# control.net
KiCad netlist of a schematic drawn in EAGLE
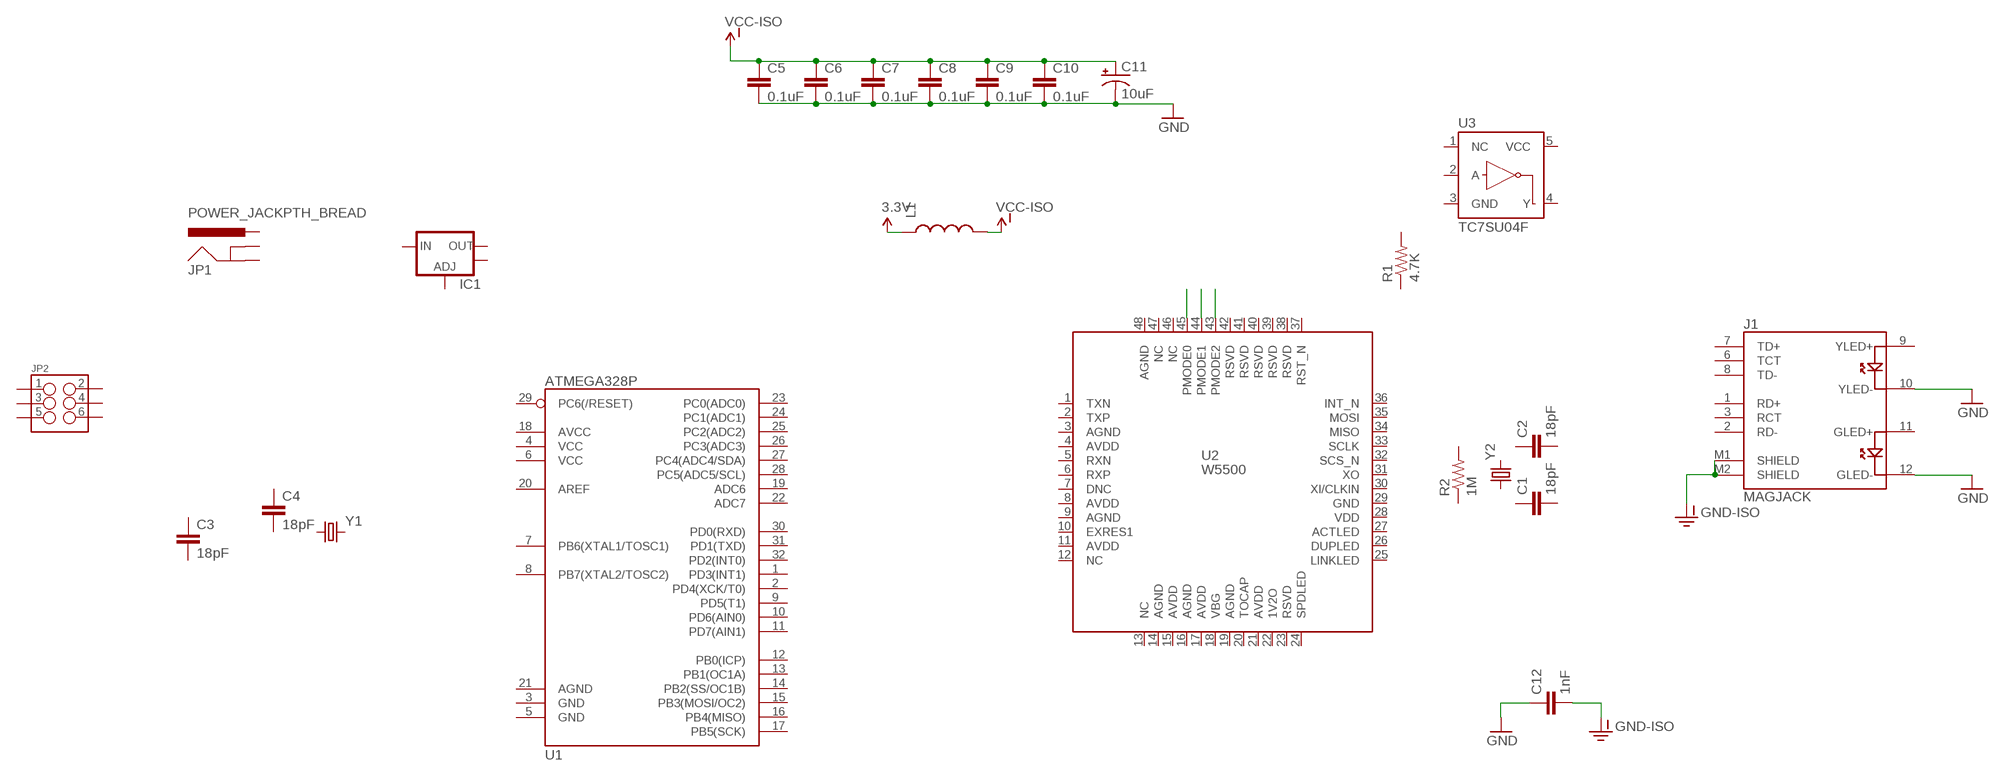
[diagram p0: schematic, sheet 1]

(export (version "E")
  (design (tool "Eeschema 10.0.6"))
  (components
    (comp (ref "C1")
      (value "18pF")
      (footprint "eagle-import:0603-CAP")
      (libsource (lib "eagle-import") (part "18PF-50V-5%(0603)"))
    )
    (comp (ref "C2")
      (value "18pF")
      (footprint "eagle-import:0603-CAP")
      (libsource (lib "eagle-import") (part "18PF-50V-5%(0603)"))
    )
    (comp (ref "C3")
      (value "18pF")
      (footprint "eagle-import:0603-CAP")
      (libsource (lib "eagle-import") (part "18PF-50V-5%(0603)"))
    )
    (comp (ref "C4")
      (value "18pF")
      (footprint "eagle-import:0603-CAP")
      (libsource (lib "eagle-import") (part "18PF-50V-5%(0603)"))
    )
    (comp (ref "C5")
      (value "0.1uF")
      (footprint "eagle-import:0603-CAP")
      (libsource (lib "eagle-import") (part "0.1UF-25V-5%(0603)"))
    )
    (comp (ref "C6")
      (value "0.1uF")
      (footprint "eagle-import:0603-CAP")
      (libsource (lib "eagle-import") (part "0.1UF-25V-5%(0603)"))
    )
    (comp (ref "C7")
      (value "0.1uF")
      (footprint "eagle-import:0603-CAP")
      (libsource (lib "eagle-import") (part "0.1UF-25V-5%(0603)"))
    )
    (comp (ref "C8")
      (value "0.1uF")
      (footprint "eagle-import:0603-CAP")
      (libsource (lib "eagle-import") (part "0.1UF-25V-5%(0603)"))
    )
    (comp (ref "C9")
      (value "0.1uF")
      (footprint "eagle-import:0603-CAP")
      (libsource (lib "eagle-import") (part "0.1UF-25V-5%(0603)"))
    )
    (comp (ref "C10")
      (value "0.1uF")
      (footprint "eagle-import:0603-CAP")
      (libsource (lib "eagle-import") (part "0.1UF-25V-5%(0603)"))
    )
    (comp (ref "C11")
      (value "10uF")
      (footprint "eagle-import:EIA3216")
      (libsource (lib "eagle-import") (part "10UF-16V-10%(TANT)"))
    )
    (comp (ref "C12")
      (value "1nF")
      (footprint "eagle-import:0603-CAP")
      (libsource (lib "eagle-import") (part "1NF/1000PF-50V-10%(0603)"))
    )
    (comp (ref "IC1")
      (value "V_REG_LM1117SOT223")
      (footprint "eagle-import:SOT223")
      (libsource (lib "eagle-import") (part "V_REG_LM1117SOT223"))
    )
    (comp (ref "J1")
      (value "MAGJACK")
      (footprint "eagle-import:MAGJACK")
      (libsource (lib "eagle-import") (part "MAGJACK"))
    )
    (comp (ref "JP1")
      (value "POWER_JACKPTH_BREAD")
      (footprint "eagle-import:POWER_JACK_PTH_BREAD")
      (libsource (lib "eagle-import") (part "POWER_JACKPTH_BREAD"))
    )
    (comp (ref "JP2")
      (value "M03X2SHROUD")
      (footprint "eagle-import:2X3-SHROUDED")
      (libsource (lib "eagle-import") (part "M03X2SHROUD"))
    )
    (comp (ref "L1")
      (value "INDUCTOR0603")
      (footprint "eagle-import:0603")
      (libsource (lib "eagle-import") (part "INDUCTOR0603"))
    )
    (comp (ref "R1")
      (value "4.7K")
      (footprint "eagle-import:0603-RES")
      (libsource (lib "eagle-import") (part "4.7KOHM-1/10W-1%(0603)"))
    )
    (comp (ref "R2")
      (value "1M")
      (footprint "eagle-import:0603-RES")
      (libsource (lib "eagle-import") (part "1MOHM-1/10W-1%(0603)"))
    )
    (comp (ref "U1")
      (value "ATMEGA328P")
      (footprint "eagle-import:TQFP32-08")
      (libsource (lib "eagle-import") (part "ATMEGA328_SMT"))
    )
    (comp (ref "U2")
      (value "W5500")
      (footprint "eagle-import:W5500")
      (libsource (lib "eagle-import") (part "W5500"))
    )
    (comp (ref "U3")
      (value "TC7SU04F")
      (footprint "eagle-import:SOT23-5")
      (libsource (lib "eagle-import") (part "INVERTER_SOT23-5"))
    )
    (comp (ref "Y1")
      (value "CRYSTALHC49US")
      (footprint "eagle-import:HC49US")
      (libsource (lib "eagle-import") (part "CRYSTALHC49US"))
    )
    (comp (ref "Y2")
      (value "CRYSTALHC49US")
      (footprint "eagle-import:HC49US")
      (libsource (lib "eagle-import") (part "CRYSTALHC49US"))
    )
  )
  (nets
    (net (code "1") (name "3.3V") (class "Default")
      (node (ref "L1") (pin "1") (pinfunction "1_1") (pintype "passive"))
    )
    (net (code "2") (name "GND") (class "Default")
      (node (ref "C10") (pin "2") (pinfunction "2_2") (pintype "passive"))
      (node (ref "C11") (pin "C") (pinfunction "-_C") (pintype "passive"))
      (node (ref "C12") (pin "1") (pinfunction "1_1") (pintype "passive"))
      (node (ref "C5") (pin "2") (pinfunction "2_2") (pintype "passive"))
      (node (ref "C6") (pin "2") (pinfunction "2_2") (pintype "passive"))
      (node (ref "C7") (pin "2") (pinfunction "2_2") (pintype "passive"))
      (node (ref "C8") (pin "2") (pinfunction "2_2") (pintype "passive"))
      (node (ref "C9") (pin "2") (pinfunction "2_2") (pintype "passive"))
      (node (ref "J1") (pin "10") (pinfunction "YLED-_10") (pintype "bidirectional"))
      (node (ref "J1") (pin "12") (pinfunction "GLED-_12") (pintype "bidirectional"))
    )
    (net (code "3") (name "GND-ISO") (class "Default")
      (node (ref "C12") (pin "2") (pinfunction "2_2") (pintype "passive"))
      (node (ref "J1") (pin "M1") (pinfunction "SHIELD_M1") (pintype "bidirectional"))
      (node (ref "J1") (pin "M2") (pinfunction "SHIELD_M2") (pintype "bidirectional"))
    )
    (net (code "4") (name "VCC-ISO") (class "Default")
      (node (ref "C10") (pin "1") (pinfunction "1_1") (pintype "passive"))
      (node (ref "C11") (pin "A") (pinfunction "+_A") (pintype "passive"))
      (node (ref "C5") (pin "1") (pinfunction "1_1") (pintype "passive"))
      (node (ref "C6") (pin "1") (pinfunction "1_1") (pintype "passive"))
      (node (ref "C7") (pin "1") (pinfunction "1_1") (pintype "passive"))
      (node (ref "C8") (pin "1") (pinfunction "1_1") (pintype "passive"))
      (node (ref "C9") (pin "1") (pinfunction "1_1") (pintype "passive"))
      (node (ref "L1") (pin "2") (pinfunction "2_2") (pintype "passive"))
    )
    (net (code "5") (name "unconnected-(C1-Pad1)") (class "Default")
      (node (ref "C1") (pin "1") (pinfunction "1_1") (pintype "passive"))
    )
    (net (code "6") (name "unconnected-(C1-Pad2)") (class "Default")
      (node (ref "C1") (pin "2") (pinfunction "2_2") (pintype "passive"))
    )
    (net (code "7") (name "unconnected-(C2-Pad1)") (class "Default")
      (node (ref "C2") (pin "1") (pinfunction "1_1") (pintype "passive"))
    )
    (net (code "8") (name "unconnected-(C2-Pad2)") (class "Default")
      (node (ref "C2") (pin "2") (pinfunction "2_2") (pintype "passive"))
    )
    (net (code "9") (name "unconnected-(C3-Pad1)") (class "Default")
      (node (ref "C3") (pin "1") (pinfunction "1_1") (pintype "passive"))
    )
    (net (code "10") (name "unconnected-(C3-Pad2)") (class "Default")
      (node (ref "C3") (pin "2") (pinfunction "2_2") (pintype "passive"))
    )
    (net (code "11") (name "unconnected-(C4-Pad1)") (class "Default")
      (node (ref "C4") (pin "1") (pinfunction "1_1") (pintype "passive"))
    )
    (net (code "12") (name "unconnected-(C4-Pad2)") (class "Default")
      (node (ref "C4") (pin "2") (pinfunction "2_2") (pintype "passive"))
    )
    (net (code "13") (name "unconnected-(IC1-ADJ-Pad1)") (class "Default")
      (node (ref "IC1") (pin "1") (pinfunction "ADJ_1") (pintype "input"))
    )
    (net (code "14") (name "unconnected-(IC1-IN-Pad3)") (class "Default")
      (node (ref "IC1") (pin "3") (pinfunction "IN_3") (pintype "input"))
    )
    (net (code "15") (name "unconnected-(IC1-OUT-Pad2)") (class "Default")
      (node (ref "IC1") (pin "2") (pinfunction "OUT_2") (pintype "output"))
    )
    (net (code "16") (name "unconnected-(IC1-OUT-Pad4)") (class "Default")
      (node (ref "IC1") (pin "4") (pinfunction "OUT_4") (pintype "output"))
    )
    (net (code "17") (name "unconnected-(J1-GLED+-Pad11)") (class "Default")
      (node (ref "J1") (pin "11") (pinfunction "GLED+_11") (pintype "bidirectional"))
    )
    (net (code "18") (name "unconnected-(J1-RCT-Pad3)") (class "Default")
      (node (ref "J1") (pin "3") (pinfunction "RCT_3") (pintype "bidirectional"))
    )
    (net (code "19") (name "unconnected-(J1-RD+-Pad1)") (class "Default")
      (node (ref "J1") (pin "1") (pinfunction "RD+_1") (pintype "bidirectional"))
    )
    (net (code "20") (name "unconnected-(J1-RD--Pad2)") (class "Default")
      (node (ref "J1") (pin "2") (pinfunction "RD-_2") (pintype "bidirectional"))
    )
    (net (code "21") (name "unconnected-(J1-TCT-Pad6)") (class "Default")
      (node (ref "J1") (pin "6") (pinfunction "TCT_6") (pintype "bidirectional"))
    )
    (net (code "22") (name "unconnected-(J1-TD+-Pad7)") (class "Default")
      (node (ref "J1") (pin "7") (pinfunction "TD+_7") (pintype "bidirectional"))
    )
    (net (code "23") (name "unconnected-(J1-TD--Pad8)") (class "Default")
      (node (ref "J1") (pin "8") (pinfunction "TD-_8") (pintype "bidirectional"))
    )
    (net (code "24") (name "unconnected-(J1-YLED+-Pad9)") (class "Default")
      (node (ref "J1") (pin "9") (pinfunction "YLED+_9") (pintype "bidirectional"))
    )
    (net (code "25") (name "unconnected-(JP1-PadGND)") (class "Default")
      (node (ref "JP1") (pin "GND") (pinfunction "GND_GND") (pintype "bidirectional"))
    )
    (net (code "26") (name "unconnected-(JP1-PadGNDBREAK)") (class "Default")
      (node (ref "JP1") (pin "GNDBREAK") (pinfunction "GNDBREAK_GNDBREAK") (pintype "bidirectional"))
    )
    (net (code "27") (name "unconnected-(JP1-PadPWR)") (class "Default")
      (node (ref "JP1") (pin "PWR") (pinfunction "PWR_PWR") (pintype "bidirectional"))
    )
    (net (code "28") (name "unconnected-(JP2-Pad1)") (class "Default")
      (node (ref "JP2") (pin "1") (pinfunction "1_1") (pintype "bidirectional"))
    )
    (net (code "29") (name "unconnected-(JP2-Pad2)") (class "Default")
      (node (ref "JP2") (pin "2") (pinfunction "2_2") (pintype "bidirectional"))
    )
    (net (code "30") (name "unconnected-(JP2-Pad3)") (class "Default")
      (node (ref "JP2") (pin "3") (pinfunction "3_3") (pintype "bidirectional"))
    )
    (net (code "31") (name "unconnected-(JP2-Pad4)") (class "Default")
      (node (ref "JP2") (pin "4") (pinfunction "4_4") (pintype "bidirectional"))
    )
    (net (code "32") (name "unconnected-(JP2-Pad5)") (class "Default")
      (node (ref "JP2") (pin "5") (pinfunction "5_5") (pintype "bidirectional"))
    )
    (net (code "33") (name "unconnected-(JP2-Pad6)") (class "Default")
      (node (ref "JP2") (pin "6") (pinfunction "6_6") (pintype "bidirectional"))
    )
    (net (code "34") (name "unconnected-(R1-Pad1)") (class "Default")
      (node (ref "R1") (pin "1") (pinfunction "1_1") (pintype "passive"))
    )
    (net (code "35") (name "unconnected-(R1-Pad2)") (class "Default")
      (node (ref "R1") (pin "2") (pinfunction "2_2") (pintype "passive"))
    )
    (net (code "36") (name "unconnected-(R2-Pad1)") (class "Default")
      (node (ref "R2") (pin "1") (pinfunction "1_1") (pintype "passive"))
    )
    (net (code "37") (name "unconnected-(R2-Pad2)") (class "Default")
      (node (ref "R2") (pin "2") (pinfunction "2_2") (pintype "passive"))
    )
    (net (code "38") (name "unconnected-(U1-ADC6-Pad19)") (class "Default")
      (node (ref "U1") (pin "19") (pinfunction "ADC6_19") (pintype "bidirectional"))
    )
    (net (code "39") (name "unconnected-(U1-ADC7-Pad22)") (class "Default")
      (node (ref "U1") (pin "22") (pinfunction "ADC7_22") (pintype "bidirectional"))
    )
    (net (code "40") (name "unconnected-(U1-AGND-Pad21)") (class "Default")
      (node (ref "U1") (pin "21") (pinfunction "AGND_21") (pintype "bidirectional"))
    )
    (net (code "41") (name "unconnected-(U1-AREF-Pad20)") (class "Default")
      (node (ref "U1") (pin "20") (pinfunction "AREF_20") (pintype "bidirectional"))
    )
    (net (code "42") (name "unconnected-(U1-AVCC-Pad18)") (class "Default")
      (node (ref "U1") (pin "18") (pinfunction "AVCC_18") (pintype "bidirectional"))
    )
    (net (code "43") (name "unconnected-(U1-GND-Pad3)") (class "Default")
      (node (ref "U1") (pin "3") (pinfunction "GND_3") (pintype "bidirectional"))
    )
    (net (code "44") (name "unconnected-(U1-GND-Pad5)") (class "Default")
      (node (ref "U1") (pin "5") (pinfunction "GND_5") (pintype "bidirectional"))
    )
    (net (code "45") (name "unconnected-(U1-PB0(ICP)-Pad12)") (class "Default")
      (node (ref "U1") (pin "12") (pinfunction "PB0(ICP)_12") (pintype "bidirectional"))
    )
    (net (code "46") (name "unconnected-(U1-PB1(OC1A)-Pad13)") (class "Default")
      (node (ref "U1") (pin "13") (pinfunction "PB1(OC1A)_13") (pintype "bidirectional"))
    )
    (net (code "47") (name "unconnected-(U1-PB2(SS{slash}OC1B)-Pad14)") (class "Default")
      (node (ref "U1") (pin "14") (pinfunction "PB2(SS/OC1B)_14") (pintype "bidirectional"))
    )
    (net (code "48") (name "unconnected-(U1-PB3(MOSI{slash}OC2)-Pad15)") (class "Default")
      (node (ref "U1") (pin "15") (pinfunction "PB3(MOSI/OC2)_15") (pintype "bidirectional"))
    )
    (net (code "49") (name "unconnected-(U1-PB4(MISO)-Pad16)") (class "Default")
      (node (ref "U1") (pin "16") (pinfunction "PB4(MISO)_16") (pintype "bidirectional"))
    )
    (net (code "50") (name "unconnected-(U1-PB5(SCK)-Pad17)") (class "Default")
      (node (ref "U1") (pin "17") (pinfunction "PB5(SCK)_17") (pintype "bidirectional"))
    )
    (net (code "51") (name "unconnected-(U1-PB6(XTAL1{slash}TOSC1)-Pad7)") (class "Default")
      (node (ref "U1") (pin "7") (pinfunction "PB6(XTAL1/TOSC1)_7") (pintype "bidirectional"))
    )
    (net (code "52") (name "unconnected-(U1-PB7(XTAL2{slash}TOSC2)-Pad8)") (class "Default")
      (node (ref "U1") (pin "8") (pinfunction "PB7(XTAL2/TOSC2)_8") (pintype "bidirectional"))
    )
    (net (code "53") (name "unconnected-(U1-PC0(ADC0)-Pad23)") (class "Default")
      (node (ref "U1") (pin "23") (pinfunction "PC0(ADC0)_23") (pintype "bidirectional"))
    )
    (net (code "54") (name "unconnected-(U1-PC1(ADC1)-Pad24)") (class "Default")
      (node (ref "U1") (pin "24") (pinfunction "PC1(ADC1)_24") (pintype "bidirectional"))
    )
    (net (code "55") (name "unconnected-(U1-PC2(ADC2)-Pad25)") (class "Default")
      (node (ref "U1") (pin "25") (pinfunction "PC2(ADC2)_25") (pintype "bidirectional"))
    )
    (net (code "56") (name "unconnected-(U1-PC3(ADC3)-Pad26)") (class "Default")
      (node (ref "U1") (pin "26") (pinfunction "PC3(ADC3)_26") (pintype "bidirectional"))
    )
    (net (code "57") (name "unconnected-(U1-PC4(ADC4{slash}SDA)-Pad27)") (class "Default")
      (node (ref "U1") (pin "27") (pinfunction "PC4(ADC4/SDA)_27") (pintype "bidirectional"))
    )
    (net (code "58") (name "unconnected-(U1-PC5(ADC5{slash}SCL)-Pad28)") (class "Default")
      (node (ref "U1") (pin "28") (pinfunction "PC5(ADC5/SCL)_28") (pintype "bidirectional"))
    )
    (net (code "59") (name "unconnected-(U1-PC6({slash}RESET)-Pad29)") (class "Default")
      (node (ref "U1") (pin "29") (pinfunction "PC6(/RESET)_29") (pintype "bidirectional"))
    )
    (net (code "60") (name "unconnected-(U1-PD0(RXD)-Pad30)") (class "Default")
      (node (ref "U1") (pin "30") (pinfunction "PD0(RXD)_30") (pintype "bidirectional"))
    )
    (net (code "61") (name "unconnected-(U1-PD1(TXD)-Pad31)") (class "Default")
      (node (ref "U1") (pin "31") (pinfunction "PD1(TXD)_31") (pintype "bidirectional"))
    )
    (net (code "62") (name "unconnected-(U1-PD2(INT0)-Pad32)") (class "Default")
      (node (ref "U1") (pin "32") (pinfunction "PD2(INT0)_32") (pintype "bidirectional"))
    )
    (net (code "63") (name "unconnected-(U1-PD3(INT1)-Pad1)") (class "Default")
      (node (ref "U1") (pin "1") (pinfunction "PD3(INT1)_1") (pintype "bidirectional"))
    )
    (net (code "64") (name "unconnected-(U1-PD4(XCK{slash}T0)-Pad2)") (class "Default")
      (node (ref "U1") (pin "2") (pinfunction "PD4(XCK/T0)_2") (pintype "bidirectional"))
    )
    (net (code "65") (name "unconnected-(U1-PD5(T1)-Pad9)") (class "Default")
      (node (ref "U1") (pin "9") (pinfunction "PD5(T1)_9") (pintype "bidirectional"))
    )
    (net (code "66") (name "unconnected-(U1-PD6(AIN0)-Pad10)") (class "Default")
      (node (ref "U1") (pin "10") (pinfunction "PD6(AIN0)_10") (pintype "bidirectional"))
    )
    (net (code "67") (name "unconnected-(U1-PD7(AIN1)-Pad11)") (class "Default")
      (node (ref "U1") (pin "11") (pinfunction "PD7(AIN1)_11") (pintype "bidirectional"))
    )
    (net (code "68") (name "unconnected-(U1-VCC-Pad4)") (class "Default")
      (node (ref "U1") (pin "4") (pinfunction "VCC_4") (pintype "bidirectional"))
    )
    (net (code "69") (name "unconnected-(U1-VCC-Pad6)") (class "Default")
      (node (ref "U1") (pin "6") (pinfunction "VCC_6") (pintype "bidirectional"))
    )
    (net (code "70") (name "unconnected-(U2-1V2O-Pad22)") (class "Default")
      (node (ref "U2") (pin "22") (pinfunction "1V2O_22") (pintype "passive"))
    )
    (net (code "71") (name "unconnected-(U2-ACTLED-Pad27)") (class "Default")
      (node (ref "U2") (pin "27") (pinfunction "ACTLED_27") (pintype "passive"))
    )
    (net (code "72") (name "unconnected-(U2-AGND-Pad3)") (class "Default")
      (node (ref "U2") (pin "3") (pinfunction "AGND_3") (pintype "passive"))
    )
    (net (code "73") (name "unconnected-(U2-AGND-Pad9)") (class "Default")
      (node (ref "U2") (pin "9") (pinfunction "AGND_9") (pintype "passive"))
    )
    (net (code "74") (name "unconnected-(U2-AGND-Pad14)") (class "Default")
      (node (ref "U2") (pin "14") (pinfunction "AGND_14") (pintype "passive"))
    )
    (net (code "75") (name "unconnected-(U2-AGND-Pad16)") (class "Default")
      (node (ref "U2") (pin "16") (pinfunction "AGND_16") (pintype "passive"))
    )
    (net (code "76") (name "unconnected-(U2-AGND-Pad19)") (class "Default")
      (node (ref "U2") (pin "19") (pinfunction "AGND_19") (pintype "passive"))
    )
    (net (code "77") (name "unconnected-(U2-AGND-Pad48)") (class "Default")
      (node (ref "U2") (pin "48") (pinfunction "AGND_48") (pintype "passive"))
    )
    (net (code "78") (name "unconnected-(U2-AVDD-Pad4)") (class "Default")
      (node (ref "U2") (pin "4") (pinfunction "AVDD_4") (pintype "passive"))
    )
    (net (code "79") (name "unconnected-(U2-AVDD-Pad8)") (class "Default")
      (node (ref "U2") (pin "8") (pinfunction "AVDD_8") (pintype "passive"))
    )
    (net (code "80") (name "unconnected-(U2-AVDD-Pad11)") (class "Default")
      (node (ref "U2") (pin "11") (pinfunction "AVDD_11") (pintype "passive"))
    )
    (net (code "81") (name "unconnected-(U2-AVDD-Pad15)") (class "Default")
      (node (ref "U2") (pin "15") (pinfunction "AVDD_15") (pintype "passive"))
    )
    (net (code "82") (name "unconnected-(U2-AVDD-Pad17)") (class "Default")
      (node (ref "U2") (pin "17") (pinfunction "AVDD_17") (pintype "passive"))
    )
    (net (code "83") (name "unconnected-(U2-AVDD-Pad21)") (class "Default")
      (node (ref "U2") (pin "21") (pinfunction "AVDD_21") (pintype "passive"))
    )
    (net (code "84") (name "unconnected-(U2-DNC-Pad7)") (class "Default")
      (node (ref "U2") (pin "7") (pinfunction "DNC_7") (pintype "passive"))
    )
    (net (code "85") (name "unconnected-(U2-DUPLED-Pad26)") (class "Default")
      (node (ref "U2") (pin "26") (pinfunction "DUPLED_26") (pintype "passive"))
    )
    (net (code "86") (name "unconnected-(U2-EXRES1-Pad10)") (class "Default")
      (node (ref "U2") (pin "10") (pinfunction "EXRES1_10") (pintype "passive"))
    )
    (net (code "87") (name "unconnected-(U2-GND-Pad29)") (class "Default")
      (node (ref "U2") (pin "29") (pinfunction "GND_29") (pintype "passive"))
    )
    (net (code "88") (name "unconnected-(U2-INT_N-Pad36)") (class "Default")
      (node (ref "U2") (pin "36") (pinfunction "INT_N_36") (pintype "passive"))
    )
    (net (code "89") (name "unconnected-(U2-LINKLED-Pad25)") (class "Default")
      (node (ref "U2") (pin "25") (pinfunction "LINKLED_25") (pintype "passive"))
    )
    (net (code "90") (name "unconnected-(U2-MISO-Pad34)") (class "Default")
      (node (ref "U2") (pin "34") (pinfunction "MISO_34") (pintype "passive"))
    )
    (net (code "91") (name "unconnected-(U2-MOSI-Pad35)") (class "Default")
      (node (ref "U2") (pin "35") (pinfunction "MOSI_35") (pintype "passive"))
    )
    (net (code "92") (name "unconnected-(U2-NC-Pad12)") (class "Default")
      (node (ref "U2") (pin "12") (pinfunction "NC_12") (pintype "passive"))
    )
    (net (code "93") (name "unconnected-(U2-NC-Pad13)") (class "Default")
      (node (ref "U2") (pin "13") (pinfunction "NC_13") (pintype "passive"))
    )
    (net (code "94") (name "unconnected-(U2-NC-Pad46)") (class "Default")
      (node (ref "U2") (pin "46") (pinfunction "NC_46") (pintype "passive"))
    )
    (net (code "95") (name "unconnected-(U2-NC-Pad47)") (class "Default")
      (node (ref "U2") (pin "47") (pinfunction "NC_47") (pintype "passive"))
    )
    (net (code "96") (name "unconnected-(U2-PMODE0-Pad45)") (class "Default")
      (node (ref "U2") (pin "45") (pinfunction "PMODE0_45") (pintype "passive"))
    )
    (net (code "97") (name "unconnected-(U2-PMODE1-Pad44)") (class "Default")
      (node (ref "U2") (pin "44") (pinfunction "PMODE1_44") (pintype "passive"))
    )
    (net (code "98") (name "unconnected-(U2-PMODE2-Pad43)") (class "Default")
      (node (ref "U2") (pin "43") (pinfunction "PMODE2_43") (pintype "passive"))
    )
    (net (code "99") (name "unconnected-(U2-RST_N-Pad37)") (class "Default")
      (node (ref "U2") (pin "37") (pinfunction "RST_N_37") (pintype "passive"))
    )
    (net (code "100") (name "unconnected-(U2-RSVD-Pad23)") (class "Default")
      (node (ref "U2") (pin "23") (pinfunction "RSVD_23") (pintype "passive"))
    )
    (net (code "101") (name "unconnected-(U2-RSVD-Pad38)") (class "Default")
      (node (ref "U2") (pin "38") (pinfunction "RSVD_38") (pintype "passive"))
    )
    (net (code "102") (name "unconnected-(U2-RSVD-Pad39)") (class "Default")
      (node (ref "U2") (pin "39") (pinfunction "RSVD_39") (pintype "passive"))
    )
    (net (code "103") (name "unconnected-(U2-RSVD-Pad40)") (class "Default")
      (node (ref "U2") (pin "40") (pinfunction "RSVD_40") (pintype "passive"))
    )
    (net (code "104") (name "unconnected-(U2-RSVD-Pad41)") (class "Default")
      (node (ref "U2") (pin "41") (pinfunction "RSVD_41") (pintype "passive"))
    )
    (net (code "105") (name "unconnected-(U2-RSVD-Pad42)") (class "Default")
      (node (ref "U2") (pin "42") (pinfunction "RSVD_42") (pintype "passive"))
    )
    (net (code "106") (name "unconnected-(U2-RXN-Pad5)") (class "Default")
      (node (ref "U2") (pin "5") (pinfunction "RXN_5") (pintype "passive"))
    )
    (net (code "107") (name "unconnected-(U2-RXP-Pad6)") (class "Default")
      (node (ref "U2") (pin "6") (pinfunction "RXP_6") (pintype "passive"))
    )
    (net (code "108") (name "unconnected-(U2-SCLK-Pad33)") (class "Default")
      (node (ref "U2") (pin "33") (pinfunction "SCLK_33") (pintype "passive"))
    )
    (net (code "109") (name "unconnected-(U2-SCS_N-Pad32)") (class "Default")
      (node (ref "U2") (pin "32") (pinfunction "SCS_N_32") (pintype "passive"))
    )
    (net (code "110") (name "unconnected-(U2-SPDLED-Pad24)") (class "Default")
      (node (ref "U2") (pin "24") (pinfunction "SPDLED_24") (pintype "passive"))
    )
    (net (code "111") (name "unconnected-(U2-TOCAP-Pad20)") (class "Default")
      (node (ref "U2") (pin "20") (pinfunction "TOCAP_20") (pintype "passive"))
    )
    (net (code "112") (name "unconnected-(U2-TXN-Pad1)") (class "Default")
      (node (ref "U2") (pin "1") (pinfunction "TXN_1") (pintype "passive"))
    )
    (net (code "113") (name "unconnected-(U2-TXP-Pad2)") (class "Default")
      (node (ref "U2") (pin "2") (pinfunction "TXP_2") (pintype "passive"))
    )
    (net (code "114") (name "unconnected-(U2-VBG-Pad18)") (class "Default")
      (node (ref "U2") (pin "18") (pinfunction "VBG_18") (pintype "passive"))
    )
    (net (code "115") (name "unconnected-(U2-VDD-Pad28)") (class "Default")
      (node (ref "U2") (pin "28") (pinfunction "VDD_28") (pintype "passive"))
    )
    (net (code "116") (name "unconnected-(U2-XI{slash}CLKIN-Pad30)") (class "Default")
      (node (ref "U2") (pin "30") (pinfunction "XI/CLKIN_30") (pintype "passive"))
    )
    (net (code "117") (name "unconnected-(U2-XO-Pad31)") (class "Default")
      (node (ref "U2") (pin "31") (pinfunction "XO_31") (pintype "passive"))
    )
    (net (code "118") (name "unconnected-(U3-A-Pad2)") (class "Default")
      (node (ref "U3") (pin "2") (pinfunction "A_2") (pintype "bidirectional"))
    )
    (net (code "119") (name "unconnected-(U3-GND-Pad3)") (class "Default")
      (node (ref "U3") (pin "3") (pinfunction "GND_3") (pintype "bidirectional"))
    )
    (net (code "120") (name "unconnected-(U3-NC-Pad1)") (class "Default")
      (node (ref "U3") (pin "1") (pinfunction "NC_1") (pintype "bidirectional"))
    )
    (net (code "121") (name "unconnected-(U3-VCC-Pad5)") (class "Default")
      (node (ref "U3") (pin "5") (pinfunction "VCC_5") (pintype "bidirectional"))
    )
    (net (code "122") (name "unconnected-(U3-Y-Pad4)") (class "Default")
      (node (ref "U3") (pin "4") (pinfunction "Y_4") (pintype "bidirectional"))
    )
    (net (code "123") (name "unconnected-(Y1-Pad1)") (class "Default")
      (node (ref "Y1") (pin "1") (pinfunction "1_1") (pintype "passive"))
    )
    (net (code "124") (name "unconnected-(Y1-Pad2)") (class "Default")
      (node (ref "Y1") (pin "2") (pinfunction "2_2") (pintype "passive"))
    )
    (net (code "125") (name "unconnected-(Y2-Pad1)") (class "Default")
      (node (ref "Y2") (pin "1") (pinfunction "1_1") (pintype "passive"))
    )
    (net (code "126") (name "unconnected-(Y2-Pad2)") (class "Default")
      (node (ref "Y2") (pin "2") (pinfunction "2_2") (pintype "passive"))
    )
  )
)
